# design.net
KiCad netlist of a schematic drawn in EAGLE
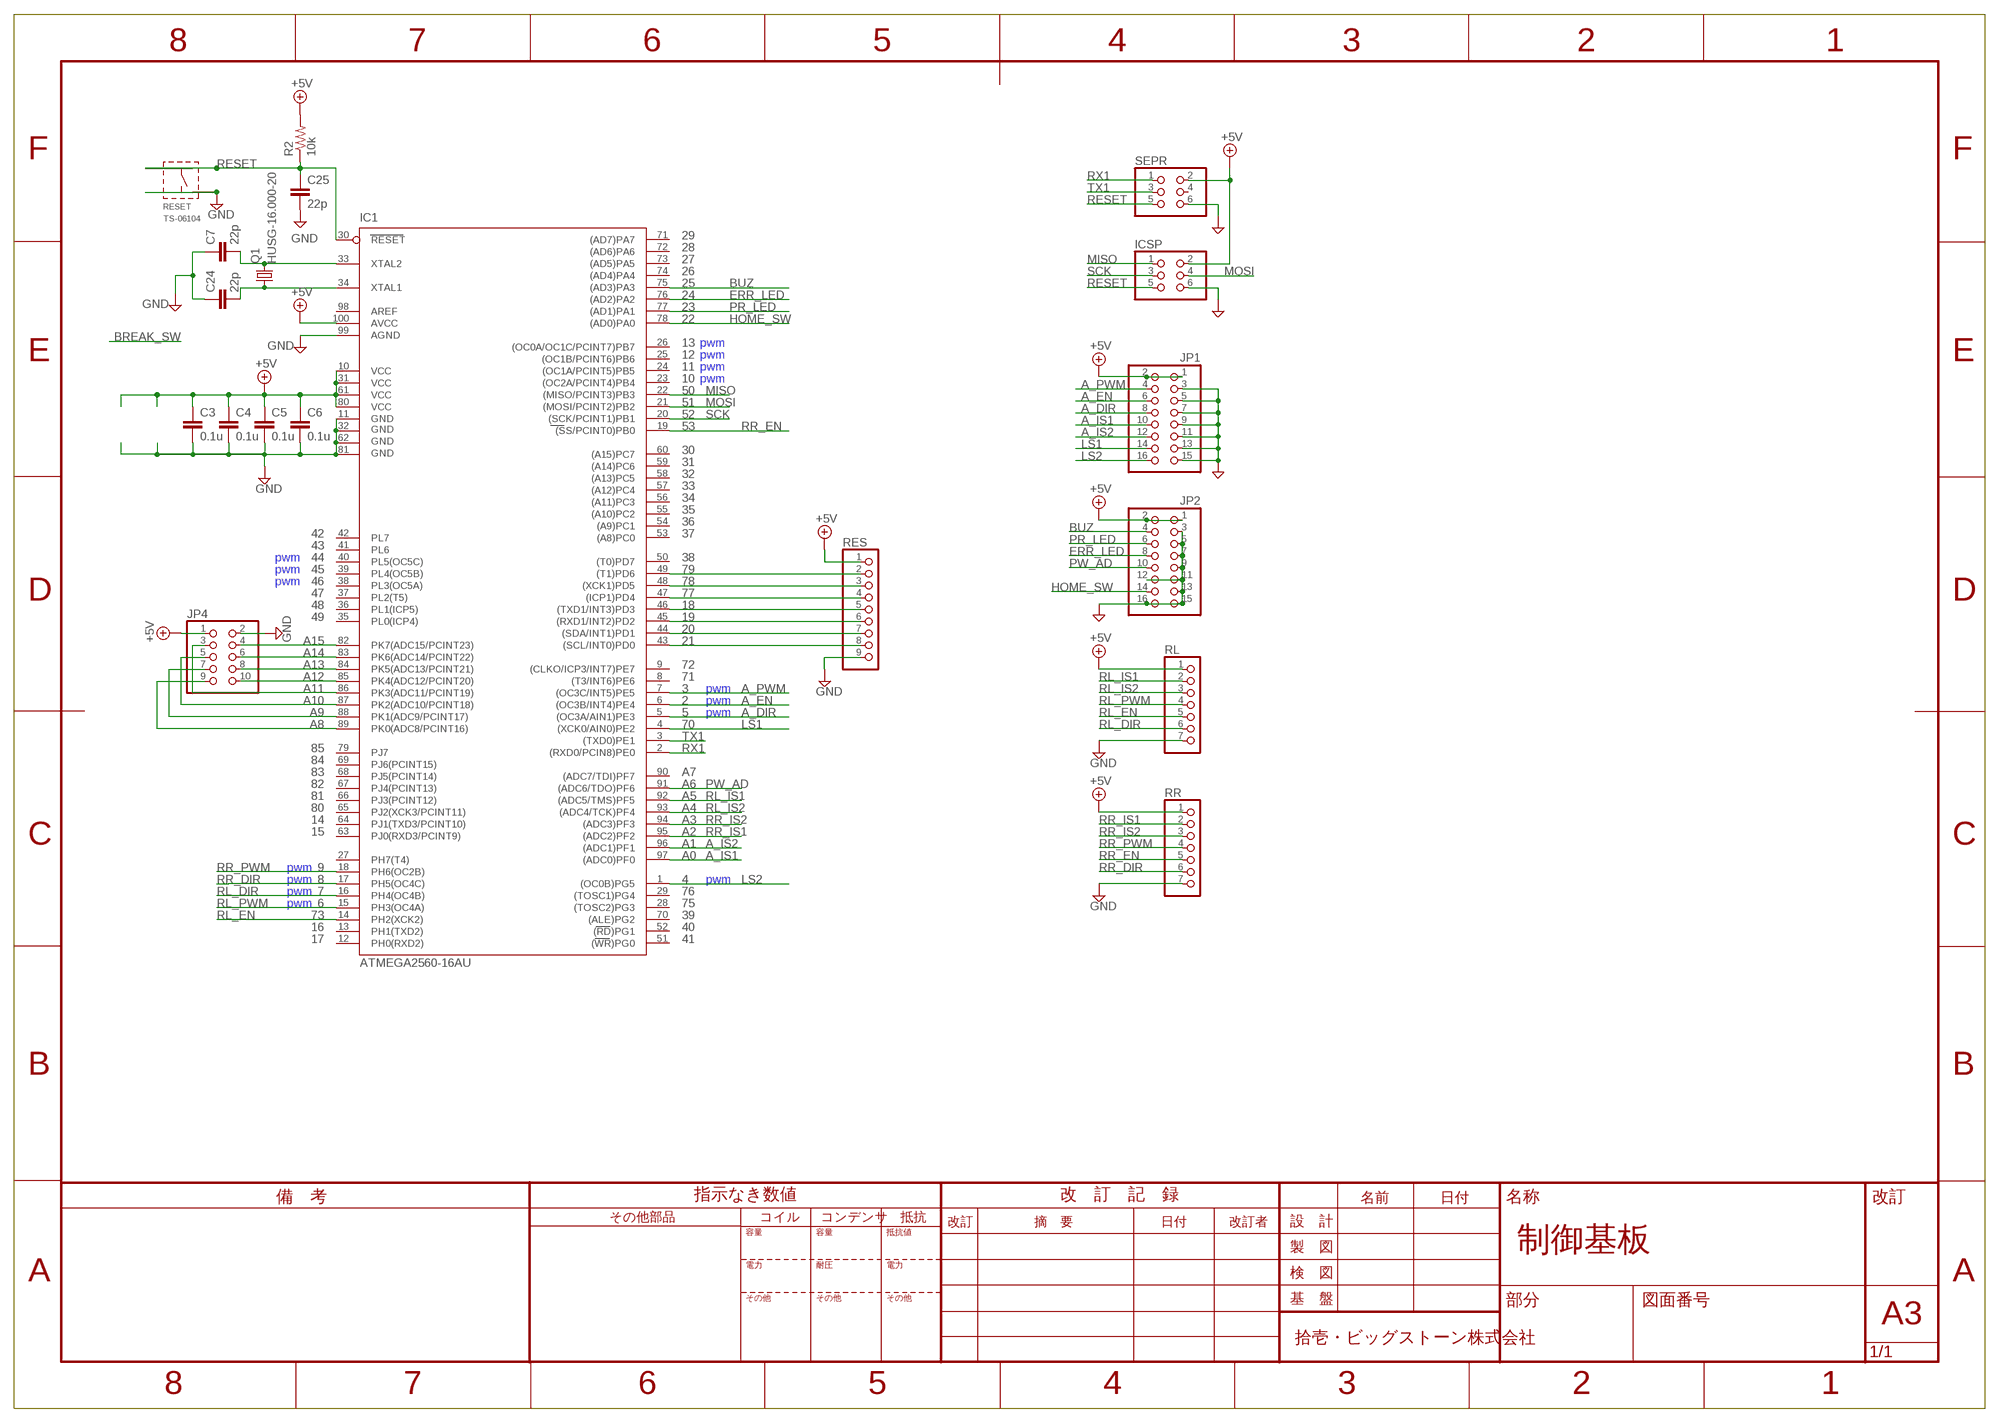
[diagram p0: schematic, sheet 1]

(export (version "E")
  (design (tool "Eeschema 10.0.6"))
  (components
    (comp (ref "C3")
      (value "0.1u")
      (footprint "eagle-import:C0603")
      (libsource (lib "eagle-import") (part "C1608"))
    )
    (comp (ref "C4")
      (value "0.1u")
      (footprint "eagle-import:C0603")
      (libsource (lib "eagle-import") (part "C1608"))
    )
    (comp (ref "C5")
      (value "0.1u")
      (footprint "eagle-import:C0603")
      (libsource (lib "eagle-import") (part "C1608"))
    )
    (comp (ref "C6")
      (value "0.1u")
      (footprint "eagle-import:C0603")
      (libsource (lib "eagle-import") (part "C1608"))
    )
    (comp (ref "C7")
      (value "22p")
      (footprint "eagle-import:C0603")
      (libsource (lib "eagle-import") (part "C1608"))
    )
    (comp (ref "C24")
      (value "22p")
      (footprint "eagle-import:C0603")
      (libsource (lib "eagle-import") (part "C1608"))
    )
    (comp (ref "C25")
      (value "22p")
      (footprint "eagle-import:C0603")
      (libsource (lib "eagle-import") (part "C1608"))
    )
    (comp (ref "IC1")
      (value "ATMEGA2560-16AU")
      (footprint "eagle-import:QFP100")
      (libsource (lib "eagle-import") (part "ATMEGA2560-16AU"))
    )
    (comp (ref "ICSP")
      (value "PINHD-2X3")
      (footprint "eagle-import:2X03")
      (libsource (lib "eagle-import") (part "PINHD-2X3"))
    )
    (comp (ref "JP1")
      (value "PINHD-2X8")
      (footprint "eagle-import:2X08")
      (libsource (lib "eagle-import") (part "PINHD-2X8"))
    )
    (comp (ref "JP2")
      (value "PINHD-2X8")
      (footprint "eagle-import:2X08")
      (libsource (lib "eagle-import") (part "PINHD-2X8"))
    )
    (comp (ref "JP4")
      (value "PINHD-2X5")
      (footprint "eagle-import:2X05")
      (libsource (lib "eagle-import") (part "PINHD-2X5"))
    )
    (comp (ref "Q1")
      (value "HUSG-16.000-20")
      (footprint "eagle-import:XTALRR480W50L990T368H350B")
      (libsource (lib "eagle-import") (part "HUSG-16.000-20"))
    )
    (comp (ref "R2")
      (value "10k")
      (footprint "eagle-import:R0603")
      (libsource (lib "eagle-import") (part "R1608"))
    )
    (comp (ref "RES")
      (value "PINHD-1X9")
      (footprint "eagle-import:1X09")
      (libsource (lib "eagle-import") (part "PINHD-1X9"))
    )
    (comp (ref "RESET")
      (value "TS-06104")
      (footprint "eagle-import:TS-06104")
      (libsource (lib "eagle-import") (part "TS-06104"))
    )
    (comp (ref "RL")
      (value "PINHD-1X7")
      (footprint "eagle-import:1X07")
      (libsource (lib "eagle-import") (part "PINHD-1X7"))
    )
    (comp (ref "RR")
      (value "PINHD-1X7")
      (footprint "eagle-import:1X07")
      (libsource (lib "eagle-import") (part "PINHD-1X7"))
    )
    (comp (ref "SEPR")
      (value "PINHD-2X3")
      (footprint "eagle-import:2X03")
      (libsource (lib "eagle-import") (part "PINHD-2X3"))
    )
  )
  (nets
    (net (code "1") (name "+5V") (class "Default")
      (node (ref "C3") (pin "1") (pinfunction "1_1") (pintype "passive"))
      (node (ref "C4") (pin "1") (pinfunction "1_1") (pintype "passive"))
      (node (ref "C5") (pin "1") (pinfunction "1_1") (pintype "passive"))
      (node (ref "C6") (pin "1") (pinfunction "1_1") (pintype "passive"))
      (node (ref "IC1") (pin "10") (pinfunction "VCC_10") (pintype "power_in"))
      (node (ref "IC1") (pin "100") (pinfunction "AVCC_100") (pintype "power_in"))
      (node (ref "IC1") (pin "31") (pinfunction "VCC1_31") (pintype "power_in"))
      (node (ref "IC1") (pin "61") (pinfunction "VCC2_61") (pintype "power_in"))
      (node (ref "IC1") (pin "80") (pinfunction "VCC3_80") (pintype "power_in"))
      (node (ref "ICSP") (pin "2") (pinfunction "2_2") (pintype "passive"))
      (node (ref "JP1") (pin "1") (pinfunction "1_1") (pintype "passive"))
      (node (ref "JP1") (pin "2") (pinfunction "2_2") (pintype "passive"))
      (node (ref "JP2") (pin "1") (pinfunction "1_1") (pintype "passive"))
      (node (ref "JP2") (pin "2") (pinfunction "2_2") (pintype "passive"))
      (node (ref "JP4") (pin "1") (pinfunction "1_1") (pintype "passive"))
      (node (ref "R2") (pin "2") (pinfunction "2_2") (pintype "passive"))
      (node (ref "RES") (pin "1") (pinfunction "1_1") (pintype "passive"))
      (node (ref "RL") (pin "1") (pinfunction "1_1") (pintype "passive"))
      (node (ref "RR") (pin "1") (pinfunction "1_1") (pintype "passive"))
      (node (ref "SEPR") (pin "2") (pinfunction "2_2") (pintype "passive"))
    )
    (net (code "2") (name "/A_DIR") (class "Default")
      (node (ref "IC1") (pin "5") (pinfunction "(OC3A/AIN1)PE3_5") (pintype "bidirectional"))
      (node (ref "JP1") (pin "8") (pinfunction "8_8") (pintype "passive"))
    )
    (net (code "3") (name "/A_EN") (class "Default")
      (node (ref "IC1") (pin "6") (pinfunction "(OC3B/INT4)PE4_6") (pintype "bidirectional"))
      (node (ref "JP1") (pin "6") (pinfunction "6_6") (pintype "passive"))
    )
    (net (code "4") (name "/A_IS1") (class "Default")
      (node (ref "IC1") (pin "97") (pinfunction "(ADC0)PF0_97") (pintype "bidirectional"))
      (node (ref "JP1") (pin "10") (pinfunction "10_10") (pintype "passive"))
    )
    (net (code "5") (name "/A_IS2") (class "Default")
      (node (ref "IC1") (pin "96") (pinfunction "(ADC1)PF1_96") (pintype "bidirectional"))
      (node (ref "JP1") (pin "12") (pinfunction "12_12") (pintype "passive"))
    )
    (net (code "6") (name "/A_PWM") (class "Default")
      (node (ref "IC1") (pin "7") (pinfunction "(OC3C/INT5)PE5_7") (pintype "bidirectional"))
      (node (ref "JP1") (pin "4") (pinfunction "4_4") (pintype "passive"))
    )
    (net (code "8") (name "/BUZ") (class "Default")
      (node (ref "IC1") (pin "75") (pinfunction "(AD3)PA3_75") (pintype "bidirectional"))
      (node (ref "JP2") (pin "4") (pinfunction "4_4") (pintype "passive"))
    )
    (net (code "9") (name "/ERR_LED") (class "Default")
      (node (ref "IC1") (pin "76") (pinfunction "(AD2)PA2_76") (pintype "bidirectional"))
      (node (ref "JP2") (pin "6") (pinfunction "6_6") (pintype "passive"))
    )
    (net (code "10") (name "/HOME_SW") (class "Default")
      (node (ref "IC1") (pin "78") (pinfunction "(AD0)PA0_78") (pintype "bidirectional"))
      (node (ref "JP2") (pin "14") (pinfunction "14_14") (pintype "passive"))
    )
    (net (code "11") (name "/LS1") (class "Default")
      (node (ref "IC1") (pin "4") (pinfunction "(XCK0/AIN0)PE2_4") (pintype "bidirectional"))
      (node (ref "JP1") (pin "14") (pinfunction "14_14") (pintype "passive"))
    )
    (net (code "12") (name "/LS2") (class "Default")
      (node (ref "IC1") (pin "1") (pinfunction "(OC0B)PG5_1") (pintype "bidirectional"))
      (node (ref "JP1") (pin "16") (pinfunction "16_16") (pintype "passive"))
    )
    (net (code "13") (name "/MISO") (class "Default")
      (node (ref "IC1") (pin "22") (pinfunction "(MISO/PCINT3)PB3_22") (pintype "bidirectional"))
      (node (ref "ICSP") (pin "1") (pinfunction "1_1") (pintype "passive"))
    )
    (net (code "14") (name "/MOSI") (class "Default")
      (node (ref "IC1") (pin "21") (pinfunction "(MOSI/PCINT2)PB2_21") (pintype "bidirectional"))
      (node (ref "ICSP") (pin "4") (pinfunction "4_4") (pintype "passive"))
    )
    (net (code "15") (name "/PR_LED") (class "Default")
      (node (ref "IC1") (pin "77") (pinfunction "(AD1)PA1_77") (pintype "bidirectional"))
      (node (ref "JP2") (pin "8") (pinfunction "8_8") (pintype "passive"))
    )
    (net (code "16") (name "/PW_AD") (class "Default")
      (node (ref "IC1") (pin "91") (pinfunction "(ADC6/TDO)PF6_91") (pintype "bidirectional"))
      (node (ref "JP2") (pin "10") (pinfunction "10_10") (pintype "passive"))
    )
    (net (code "17") (name "/RESET") (class "Default")
      (node (ref "C25") (pin "1") (pinfunction "1_1") (pintype "passive"))
      (node (ref "IC1") (pin "30") (pinfunction "RESET_30") (pintype "input"))
      (node (ref "ICSP") (pin "5") (pinfunction "5_5") (pintype "passive"))
      (node (ref "R2") (pin "1") (pinfunction "1_1") (pintype "passive"))
      (node (ref "RESET") (pin "A1") (pinfunction "T1_A1") (pintype "bidirectional"))
      (node (ref "RESET") (pin "A2") (pinfunction "T2_A2") (pintype "bidirectional"))
      (node (ref "SEPR") (pin "5") (pinfunction "5_5") (pintype "passive"))
    )
    (net (code "18") (name "/RL_DIR") (class "Default")
      (node (ref "IC1") (pin "16") (pinfunction "PH4(OC4B)_16") (pintype "bidirectional"))
      (node (ref "RL") (pin "6") (pinfunction "6_6") (pintype "passive"))
    )
    (net (code "19") (name "/RL_EN") (class "Default")
      (node (ref "IC1") (pin "14") (pinfunction "PH2(XCK2)_14") (pintype "bidirectional"))
      (node (ref "RL") (pin "5") (pinfunction "5_5") (pintype "passive"))
    )
    (net (code "20") (name "/RL_IS1") (class "Default")
      (node (ref "IC1") (pin "92") (pinfunction "(ADC5/TMS)PF5_92") (pintype "bidirectional"))
      (node (ref "RL") (pin "2") (pinfunction "2_2") (pintype "passive"))
    )
    (net (code "21") (name "/RL_IS2") (class "Default")
      (node (ref "IC1") (pin "93") (pinfunction "(ADC4/TCK)PF4_93") (pintype "bidirectional"))
      (node (ref "RL") (pin "3") (pinfunction "3_3") (pintype "passive"))
    )
    (net (code "22") (name "/RL_PWM") (class "Default")
      (node (ref "IC1") (pin "15") (pinfunction "PH3(OC4A)_15") (pintype "bidirectional"))
      (node (ref "RL") (pin "4") (pinfunction "4_4") (pintype "passive"))
    )
    (net (code "23") (name "/RR_DIR") (class "Default")
      (node (ref "IC1") (pin "17") (pinfunction "PH5(OC4C)_17") (pintype "bidirectional"))
      (node (ref "RR") (pin "6") (pinfunction "6_6") (pintype "passive"))
    )
    (net (code "24") (name "/RR_EN") (class "Default")
      (node (ref "IC1") (pin "19") (pinfunction "(SS/PCINT0)PB0_19") (pintype "bidirectional"))
      (node (ref "RR") (pin "5") (pinfunction "5_5") (pintype "passive"))
    )
    (net (code "25") (name "/RR_IS1") (class "Default")
      (node (ref "IC1") (pin "95") (pinfunction "(ADC2)PF2_95") (pintype "bidirectional"))
      (node (ref "RR") (pin "2") (pinfunction "2_2") (pintype "passive"))
    )
    (net (code "26") (name "/RR_IS2") (class "Default")
      (node (ref "IC1") (pin "94") (pinfunction "(ADC3)PF3_94") (pintype "bidirectional"))
      (node (ref "RR") (pin "3") (pinfunction "3_3") (pintype "passive"))
    )
    (net (code "27") (name "/RR_PWM") (class "Default")
      (node (ref "IC1") (pin "18") (pinfunction "PH6(OC2B)_18") (pintype "bidirectional"))
      (node (ref "RR") (pin "4") (pinfunction "4_4") (pintype "passive"))
    )
    (net (code "28") (name "/RX1") (class "Default")
      (node (ref "IC1") (pin "2") (pinfunction "(RXD0/PCIN8)PE0_2") (pintype "bidirectional"))
      (node (ref "SEPR") (pin "1") (pinfunction "1_1") (pintype "passive"))
    )
    (net (code "29") (name "/SCK") (class "Default")
      (node (ref "IC1") (pin "20") (pinfunction "(SCK/PCINT1)PB1_20") (pintype "bidirectional"))
      (node (ref "ICSP") (pin "3") (pinfunction "3_3") (pintype "passive"))
    )
    (net (code "30") (name "/TX1") (class "Default")
      (node (ref "IC1") (pin "3") (pinfunction "(TXD0)PE1_3") (pintype "bidirectional"))
      (node (ref "SEPR") (pin "3") (pinfunction "3_3") (pintype "passive"))
    )
    (net (code "31") (name "GND") (class "Default")
      (node (ref "C24") (pin "1") (pinfunction "1_1") (pintype "passive"))
      (node (ref "C25") (pin "2") (pinfunction "2_2") (pintype "passive"))
      (node (ref "C3") (pin "2") (pinfunction "2_2") (pintype "passive"))
      (node (ref "C4") (pin "2") (pinfunction "2_2") (pintype "passive"))
      (node (ref "C5") (pin "2") (pinfunction "2_2") (pintype "passive"))
      (node (ref "C6") (pin "2") (pinfunction "2_2") (pintype "passive"))
      (node (ref "C7") (pin "1") (pinfunction "1_1") (pintype "passive"))
      (node (ref "IC1") (pin "11") (pinfunction "GND_11") (pintype "power_in"))
      (node (ref "IC1") (pin "32") (pinfunction "GND1_32") (pintype "power_in"))
      (node (ref "IC1") (pin "62") (pinfunction "GND2_62") (pintype "power_in"))
      (node (ref "IC1") (pin "81") (pinfunction "GND3_81") (pintype "power_in"))
      (node (ref "IC1") (pin "99") (pinfunction "AGND_99") (pintype "power_in"))
      (node (ref "ICSP") (pin "6") (pinfunction "6_6") (pintype "passive"))
      (node (ref "JP1") (pin "11") (pinfunction "11_11") (pintype "passive"))
      (node (ref "JP1") (pin "13") (pinfunction "13_13") (pintype "passive"))
      (node (ref "JP1") (pin "15") (pinfunction "15_15") (pintype "passive"))
      (node (ref "JP1") (pin "3") (pinfunction "3_3") (pintype "passive"))
      (node (ref "JP1") (pin "5") (pinfunction "5_5") (pintype "passive"))
      (node (ref "JP1") (pin "7") (pinfunction "7_7") (pintype "passive"))
      (node (ref "JP1") (pin "9") (pinfunction "9_9") (pintype "passive"))
      (node (ref "JP2") (pin "11") (pinfunction "11_11") (pintype "passive"))
      (node (ref "JP2") (pin "12") (pinfunction "12_12") (pintype "passive"))
      (node (ref "JP2") (pin "13") (pinfunction "13_13") (pintype "passive"))
      (node (ref "JP2") (pin "15") (pinfunction "15_15") (pintype "passive"))
      (node (ref "JP2") (pin "16") (pinfunction "16_16") (pintype "passive"))
      (node (ref "JP2") (pin "3") (pinfunction "3_3") (pintype "passive"))
      (node (ref "JP2") (pin "5") (pinfunction "5_5") (pintype "passive"))
      (node (ref "JP2") (pin "7") (pinfunction "7_7") (pintype "passive"))
      (node (ref "JP2") (pin "9") (pinfunction "9_9") (pintype "passive"))
      (node (ref "JP4") (pin "2") (pinfunction "2_2") (pintype "passive"))
      (node (ref "RES") (pin "9") (pinfunction "9_9") (pintype "passive"))
      (node (ref "RESET") (pin "B1") (pinfunction "T3_B1") (pintype "bidirectional"))
      (node (ref "RESET") (pin "B2") (pinfunction "T4_B2") (pintype "bidirectional"))
      (node (ref "RL") (pin "7") (pinfunction "7_7") (pintype "passive"))
      (node (ref "RR") (pin "7") (pinfunction "7_7") (pintype "passive"))
      (node (ref "SEPR") (pin "6") (pinfunction "6_6") (pintype "passive"))
    )
    (net (code "32") (name "Net-(IC1-(ICP1)PD4)") (class "Default")
      (node (ref "IC1") (pin "47") (pinfunction "(ICP1)PD4_47") (pintype "bidirectional"))
      (node (ref "RES") (pin "4") (pinfunction "4_4") (pintype "passive"))
    )
    (net (code "33") (name "Net-(IC1-(RXD1{slash}INT2)PD2)") (class "Default")
      (node (ref "IC1") (pin "45") (pinfunction "(RXD1/INT2)PD2_45") (pintype "bidirectional"))
      (node (ref "RES") (pin "6") (pinfunction "6_6") (pintype "passive"))
    )
    (net (code "34") (name "Net-(IC1-(SCL{slash}INT0)PD0)") (class "Default")
      (node (ref "IC1") (pin "43") (pinfunction "(SCL/INT0)PD0_43") (pintype "bidirectional"))
      (node (ref "RES") (pin "8") (pinfunction "8_8") (pintype "passive"))
    )
    (net (code "35") (name "Net-(IC1-(SDA{slash}INT1)PD1)") (class "Default")
      (node (ref "IC1") (pin "44") (pinfunction "(SDA/INT1)PD1_44") (pintype "bidirectional"))
      (node (ref "RES") (pin "7") (pinfunction "7_7") (pintype "passive"))
    )
    (net (code "36") (name "Net-(IC1-(T1)PD6)") (class "Default")
      (node (ref "IC1") (pin "49") (pinfunction "(T1)PD6_49") (pintype "bidirectional"))
      (node (ref "RES") (pin "2") (pinfunction "2_2") (pintype "passive"))
    )
    (net (code "37") (name "Net-(IC1-(TXD1{slash}INT3)PD3)") (class "Default")
      (node (ref "IC1") (pin "46") (pinfunction "(TXD1/INT3)PD3_46") (pintype "bidirectional"))
      (node (ref "RES") (pin "5") (pinfunction "5_5") (pintype "passive"))
    )
    (net (code "38") (name "Net-(IC1-(XCK1)PD5)") (class "Default")
      (node (ref "IC1") (pin "48") (pinfunction "(XCK1)PD5_48") (pintype "bidirectional"))
      (node (ref "RES") (pin "3") (pinfunction "3_3") (pintype "passive"))
    )
    (net (code "39") (name "Net-(IC1-PK0(ADC8{slash}PCINT16))") (class "Default")
      (node (ref "IC1") (pin "89") (pinfunction "PK0(ADC8/PCINT16)_89") (pintype "bidirectional"))
      (node (ref "JP4") (pin "9") (pinfunction "9_9") (pintype "passive"))
    )
    (net (code "40") (name "Net-(IC1-PK1(ADC9{slash}PCINT17))") (class "Default")
      (node (ref "IC1") (pin "88") (pinfunction "PK1(ADC9/PCINT17)_88") (pintype "bidirectional"))
      (node (ref "JP4") (pin "7") (pinfunction "7_7") (pintype "passive"))
    )
    (net (code "41") (name "Net-(IC1-PK2(ADC10{slash}PCINT18))") (class "Default")
      (node (ref "IC1") (pin "87") (pinfunction "PK2(ADC10/PCINT18)_87") (pintype "bidirectional"))
      (node (ref "JP4") (pin "5") (pinfunction "5_5") (pintype "passive"))
    )
    (net (code "42") (name "Net-(IC1-PK3(ADC11{slash}PCINT19))") (class "Default")
      (node (ref "IC1") (pin "86") (pinfunction "PK3(ADC11/PCINT19)_86") (pintype "bidirectional"))
      (node (ref "JP4") (pin "3") (pinfunction "3_3") (pintype "passive"))
    )
    (net (code "43") (name "Net-(IC1-PK4(ADC12{slash}PCINT20))") (class "Default")
      (node (ref "IC1") (pin "85") (pinfunction "PK4(ADC12/PCINT20)_85") (pintype "bidirectional"))
      (node (ref "JP4") (pin "10") (pinfunction "10_10") (pintype "passive"))
    )
    (net (code "44") (name "Net-(IC1-PK5(ADC13{slash}PCINT21))") (class "Default")
      (node (ref "IC1") (pin "84") (pinfunction "PK5(ADC13/PCINT21)_84") (pintype "bidirectional"))
      (node (ref "JP4") (pin "8") (pinfunction "8_8") (pintype "passive"))
    )
    (net (code "45") (name "Net-(IC1-PK6(ADC14{slash}PCINT22))") (class "Default")
      (node (ref "IC1") (pin "83") (pinfunction "PK6(ADC14/PCINT22)_83") (pintype "bidirectional"))
      (node (ref "JP4") (pin "6") (pinfunction "6_6") (pintype "passive"))
    )
    (net (code "46") (name "Net-(IC1-PK7(ADC15{slash}PCINT23))") (class "Default")
      (node (ref "IC1") (pin "82") (pinfunction "PK7(ADC15/PCINT23)_82") (pintype "bidirectional"))
      (node (ref "JP4") (pin "4") (pinfunction "4_4") (pintype "passive"))
    )
    (net (code "47") (name "Net-(IC1-XTAL1)") (class "Default")
      (node (ref "C24") (pin "2") (pinfunction "2_2") (pintype "passive"))
      (node (ref "IC1") (pin "34") (pinfunction "XTAL1_34") (pintype "input"))
      (node (ref "Q1") (pin "1") (pinfunction "1_1") (pintype "passive"))
    )
    (net (code "48") (name "Net-(IC1-XTAL2)") (class "Default")
      (node (ref "C7") (pin "2") (pinfunction "2_2") (pintype "passive"))
      (node (ref "IC1") (pin "33") (pinfunction "XTAL2_33") (pintype "output"))
      (node (ref "Q1") (pin "2") (pinfunction "2_2") (pintype "passive"))
    )
    (net (code "49") (name "unconnected-(IC1-(A8)PC0-Pad53)") (class "Default")
      (node (ref "IC1") (pin "53") (pinfunction "(A8)PC0_53") (pintype "bidirectional"))
    )
    (net (code "50") (name "unconnected-(IC1-(A9)PC1-Pad54)") (class "Default")
      (node (ref "IC1") (pin "54") (pinfunction "(A9)PC1_54") (pintype "bidirectional"))
    )
    (net (code "51") (name "unconnected-(IC1-(A10)PC2-Pad55)") (class "Default")
      (node (ref "IC1") (pin "55") (pinfunction "(A10)PC2_55") (pintype "bidirectional"))
    )
    (net (code "52") (name "unconnected-(IC1-(A11)PC3-Pad56)") (class "Default")
      (node (ref "IC1") (pin "56") (pinfunction "(A11)PC3_56") (pintype "bidirectional"))
    )
    (net (code "53") (name "unconnected-(IC1-(A12)PC4-Pad57)") (class "Default")
      (node (ref "IC1") (pin "57") (pinfunction "(A12)PC4_57") (pintype "bidirectional"))
    )
    (net (code "54") (name "unconnected-(IC1-(A13)PC5-Pad58)") (class "Default")
      (node (ref "IC1") (pin "58") (pinfunction "(A13)PC5_58") (pintype "bidirectional"))
    )
    (net (code "55") (name "unconnected-(IC1-(A14)PC6-Pad59)") (class "Default")
      (node (ref "IC1") (pin "59") (pinfunction "(A14)PC6_59") (pintype "bidirectional"))
    )
    (net (code "56") (name "unconnected-(IC1-(A15)PC7-Pad60)") (class "Default")
      (node (ref "IC1") (pin "60") (pinfunction "(A15)PC7_60") (pintype "bidirectional"))
    )
    (net (code "57") (name "unconnected-(IC1-(AD4)PA4-Pad74)") (class "Default")
      (node (ref "IC1") (pin "74") (pinfunction "(AD4)PA4_74") (pintype "bidirectional"))
    )
    (net (code "58") (name "unconnected-(IC1-(AD5)PA5-Pad73)") (class "Default")
      (node (ref "IC1") (pin "73") (pinfunction "(AD5)PA5_73") (pintype "bidirectional"))
    )
    (net (code "59") (name "unconnected-(IC1-(AD6)PA6-Pad72)") (class "Default")
      (node (ref "IC1") (pin "72") (pinfunction "(AD6)PA6_72") (pintype "bidirectional"))
    )
    (net (code "60") (name "unconnected-(IC1-(AD7)PA7-Pad71)") (class "Default")
      (node (ref "IC1") (pin "71") (pinfunction "(AD7)PA7_71") (pintype "bidirectional"))
    )
    (net (code "61") (name "unconnected-(IC1-(ADC7{slash}TDI)PF7-Pad90)") (class "Default")
      (node (ref "IC1") (pin "90") (pinfunction "(ADC7/TDI)PF7_90") (pintype "bidirectional"))
    )
    (net (code "62") (name "unconnected-(IC1-(ALE)PG2-Pad70)") (class "Default")
      (node (ref "IC1") (pin "70") (pinfunction "(ALE)PG2_70") (pintype "bidirectional"))
    )
    (net (code "63") (name "unconnected-(IC1-(CLKO{slash}ICP3{slash}INT7)PE7-Pad9)") (class "Default")
      (node (ref "IC1") (pin "9") (pinfunction "(CLKO/ICP3/INT7)PE7_9") (pintype "bidirectional"))
    )
    (net (code "64") (name "unconnected-(IC1-(OC0A{slash}OC1C{slash}PCINT7)PB7-Pad26)") (class "Default")
      (node (ref "IC1") (pin "26") (pinfunction "(OC0A/OC1C/PCINT7)PB7_26") (pintype "bidirectional"))
    )
    (net (code "65") (name "unconnected-(IC1-(OC1A{slash}PCINT5)PB5-Pad24)") (class "Default")
      (node (ref "IC1") (pin "24") (pinfunction "(OC1A/PCINT5)PB5_24") (pintype "bidirectional"))
    )
    (net (code "66") (name "unconnected-(IC1-(OC1B{slash}PCINT6)PB6-Pad25)") (class "Default")
      (node (ref "IC1") (pin "25") (pinfunction "(OC1B/PCINT6)PB6_25") (pintype "bidirectional"))
    )
    (net (code "67") (name "unconnected-(IC1-(OC2A{slash}PCINT4)PB4-Pad23)") (class "Default")
      (node (ref "IC1") (pin "23") (pinfunction "(OC2A/PCINT4)PB4_23") (pintype "bidirectional"))
    )
    (net (code "68") (name "unconnected-(IC1-(RD)PG1-Pad52)") (class "Default")
      (node (ref "IC1") (pin "52") (pinfunction "(RD)PG1_52") (pintype "bidirectional"))
    )
    (net (code "69") (name "unconnected-(IC1-(T0)PD7-Pad50)") (class "Default")
      (node (ref "IC1") (pin "50") (pinfunction "(T0)PD7_50") (pintype "bidirectional"))
    )
    (net (code "70") (name "unconnected-(IC1-(T3{slash}INT6)PE6-Pad8)") (class "Default")
      (node (ref "IC1") (pin "8") (pinfunction "(T3/INT6)PE6_8") (pintype "bidirectional"))
    )
    (net (code "71") (name "unconnected-(IC1-(TOSC1)PG4-Pad29)") (class "Default")
      (node (ref "IC1") (pin "29") (pinfunction "(TOSC1)PG4_29") (pintype "bidirectional"))
    )
    (net (code "72") (name "unconnected-(IC1-(TOSC2)PG3-Pad28)") (class "Default")
      (node (ref "IC1") (pin "28") (pinfunction "(TOSC2)PG3_28") (pintype "bidirectional"))
    )
    (net (code "73") (name "unconnected-(IC1-(WR)PG0-Pad51)") (class "Default")
      (node (ref "IC1") (pin "51") (pinfunction "(WR)PG0_51") (pintype "bidirectional"))
    )
    (net (code "74") (name "unconnected-(IC1-AREF-Pad98)") (class "Default")
      (node (ref "IC1") (pin "98") (pinfunction "AREF_98") (pintype "bidirectional"))
    )
    (net (code "75") (name "unconnected-(IC1-PH0(RXD2)-Pad12)") (class "Default")
      (node (ref "IC1") (pin "12") (pinfunction "PH0(RXD2)_12") (pintype "bidirectional"))
    )
    (net (code "76") (name "unconnected-(IC1-PH1(TXD2)-Pad13)") (class "Default")
      (node (ref "IC1") (pin "13") (pinfunction "PH1(TXD2)_13") (pintype "bidirectional"))
    )
    (net (code "77") (name "unconnected-(IC1-PH7(T4)-Pad27)") (class "Default")
      (node (ref "IC1") (pin "27") (pinfunction "PH7(T4)_27") (pintype "bidirectional"))
    )
    (net (code "78") (name "unconnected-(IC1-PJ0(RXD3{slash}PCINT9)-Pad63)") (class "Default")
      (node (ref "IC1") (pin "63") (pinfunction "PJ0(RXD3/PCINT9)_63") (pintype "bidirectional"))
    )
    (net (code "79") (name "unconnected-(IC1-PJ1(TXD3{slash}PCINT10)-Pad64)") (class "Default")
      (node (ref "IC1") (pin "64") (pinfunction "PJ1(TXD3/PCINT10)_64") (pintype "bidirectional"))
    )
    (net (code "80") (name "unconnected-(IC1-PJ2(XCK3{slash}PCINT11)-Pad65)") (class "Default")
      (node (ref "IC1") (pin "65") (pinfunction "PJ2(XCK3/PCINT11)_65") (pintype "bidirectional"))
    )
    (net (code "81") (name "unconnected-(IC1-PJ3(PCINT12)-Pad66)") (class "Default")
      (node (ref "IC1") (pin "66") (pinfunction "PJ3(PCINT12)_66") (pintype "bidirectional"))
    )
    (net (code "82") (name "unconnected-(IC1-PJ4(PCINT13)-Pad67)") (class "Default")
      (node (ref "IC1") (pin "67") (pinfunction "PJ4(PCINT13)_67") (pintype "bidirectional"))
    )
    (net (code "83") (name "unconnected-(IC1-PJ5(PCINT14)-Pad68)") (class "Default")
      (node (ref "IC1") (pin "68") (pinfunction "PJ5(PCINT14)_68") (pintype "bidirectional"))
    )
    (net (code "84") (name "unconnected-(IC1-PJ6(PCINT15)-Pad69)") (class "Default")
      (node (ref "IC1") (pin "69") (pinfunction "PJ6(PCINT15)_69") (pintype "bidirectional"))
    )
    (net (code "85") (name "unconnected-(IC1-PJ7-Pad79)") (class "Default")
      (node (ref "IC1") (pin "79") (pinfunction "PJ7_79") (pintype "bidirectional"))
    )
    (net (code "86") (name "unconnected-(IC1-PL0(ICP4)-Pad35)") (class "Default")
      (node (ref "IC1") (pin "35") (pinfunction "PL0(ICP4)_35") (pintype "bidirectional"))
    )
    (net (code "87") (name "unconnected-(IC1-PL1(ICP5)-Pad36)") (class "Default")
      (node (ref "IC1") (pin "36") (pinfunction "PL1(ICP5)_36") (pintype "bidirectional"))
    )
    (net (code "88") (name "unconnected-(IC1-PL2(T5)-Pad37)") (class "Default")
      (node (ref "IC1") (pin "37") (pinfunction "PL2(T5)_37") (pintype "bidirectional"))
    )
    (net (code "89") (name "unconnected-(IC1-PL3(OC5A)-Pad38)") (class "Default")
      (node (ref "IC1") (pin "38") (pinfunction "PL3(OC5A)_38") (pintype "bidirectional"))
    )
    (net (code "90") (name "unconnected-(IC1-PL4(OC5B)-Pad39)") (class "Default")
      (node (ref "IC1") (pin "39") (pinfunction "PL4(OC5B)_39") (pintype "bidirectional"))
    )
    (net (code "91") (name "unconnected-(IC1-PL5(OC5C)-Pad40)") (class "Default")
      (node (ref "IC1") (pin "40") (pinfunction "PL5(OC5C)_40") (pintype "bidirectional"))
    )
    (net (code "92") (name "unconnected-(IC1-PL6-Pad41)") (class "Default")
      (node (ref "IC1") (pin "41") (pinfunction "PL6_41") (pintype "bidirectional"))
    )
    (net (code "93") (name "unconnected-(IC1-PL7-Pad42)") (class "Default")
      (node (ref "IC1") (pin "42") (pinfunction "PL7_42") (pintype "bidirectional"))
    )
    (net (code "94") (name "unconnected-(SEPR-Pad4)") (class "Default")
      (node (ref "SEPR") (pin "4") (pinfunction "4_4") (pintype "passive"))
    )
  )
)
